# KC_BaseBoard4CompareTest-V0_2.net
KiCad netlist of a schematic drawn in Altium Designer
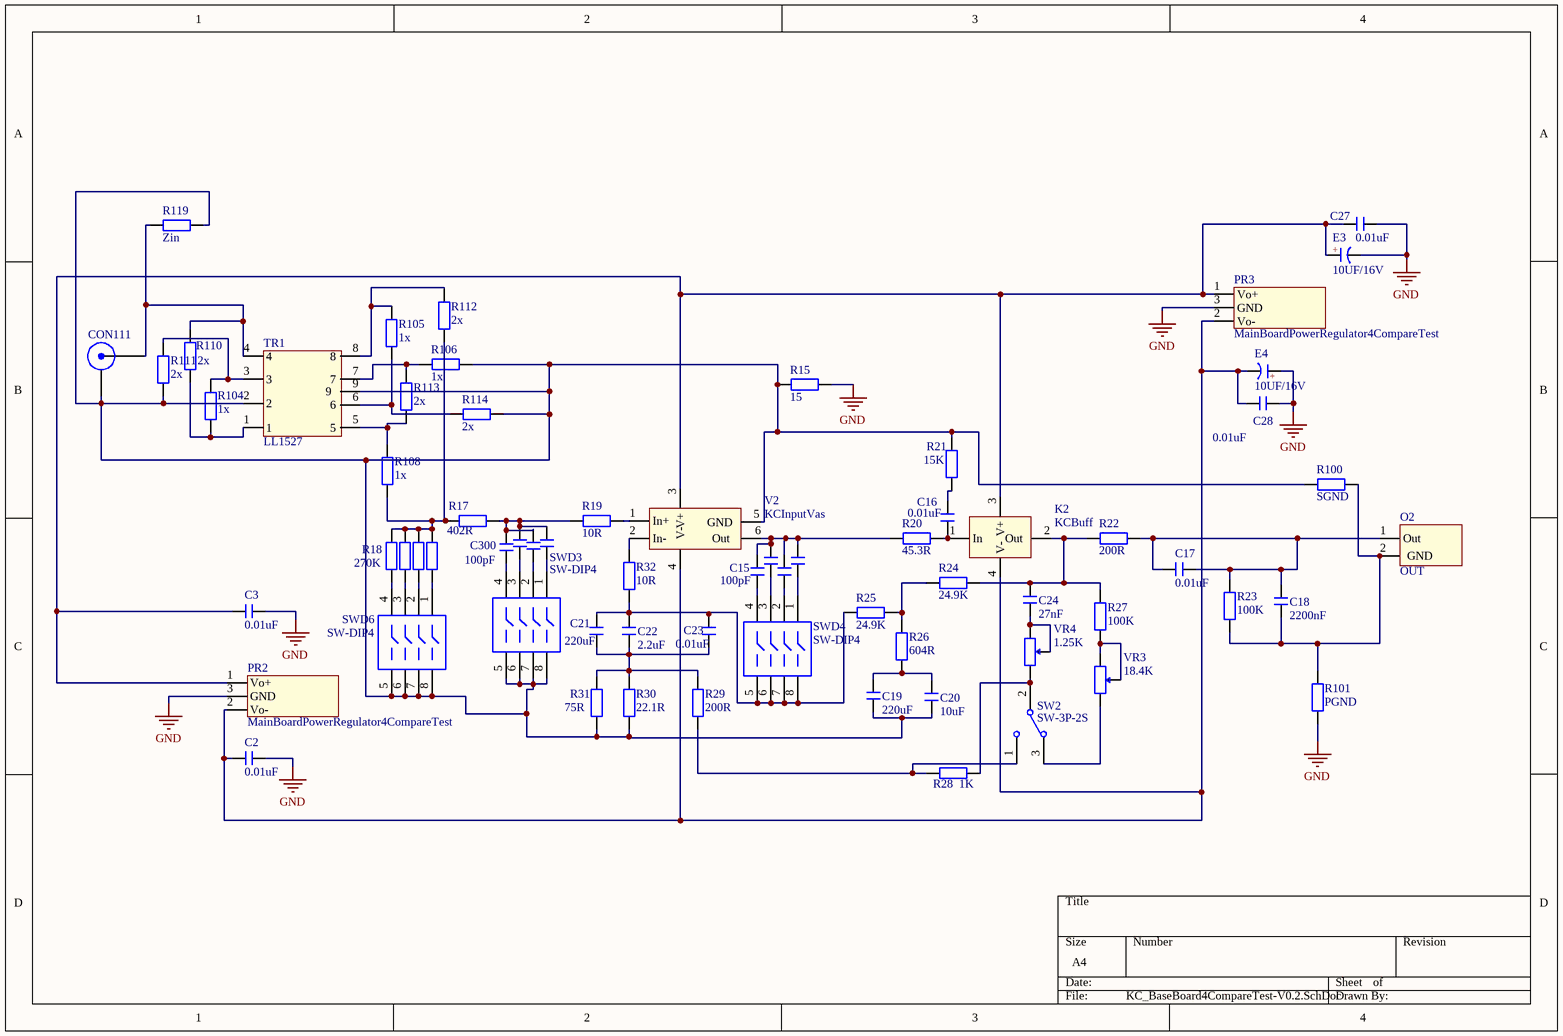
[diagram p0: KC_BaseBoard4CompareTest-V0.2.SchDoc]

(export (version "E")
  (design (tool "Eeschema 10.0.6"))
  (components
    (comp (ref "C2")
      (value "0.01uF")
      (footprint "CBB 6.3*6.3*5")
      (description "CBB电容")
      (fields (field (name "版权归属") "源创客"))
      (libsource (lib "电阻-电容-电感") (part "C-CBB"))
    )
    (comp (ref "C3")
      (value "0.01uF")
      (footprint "CBB 6.3*6.3*5")
      (description "CBB电容")
      (fields (field (name "版权归属") "源创客"))
      (libsource (lib "电阻-电容-电感") (part "C-CBB"))
    )
    (comp (ref "C15")
      (value "100pF")
      (footprint "CBB 6.3*6.3*5")
      (description "CBB电容")
      (fields (field (name "版权归属") "源创客"))
      (libsource (lib "电阻-电容-电感") (part "C-CBB"))
    )
    (comp (ref "C16")
      (value "0.01uF")
      (footprint "CBB 6.3*6.3*5")
      (description "CBB电容")
      (fields (field (name "版权归属") "源创客"))
      (libsource (lib "电阻-电容-电感") (part "C-CBB"))
    )
    (comp (ref "C17")
      (value "0.01uF")
      (footprint "CBB 6.3*6.3*5")
      (description "CBB电容")
      (fields (field (name "版权归属") "源创客"))
      (libsource (lib "电阻-电容-电感") (part "C-CBB"))
    )
    (comp (ref "C18")
      (value "2200nF")
      (footprint "CBB 6.3*6.3*5")
      (description "CBB电容")
      (fields (field (name "版权归属") "源创客"))
      (libsource (lib "电阻-电容-电感") (part "C-CBB"))
    )
    (comp (ref "C19")
      (value "220uF")
      (footprint "CBB 6.3*6.3*5")
      (description "CBB电容")
      (fields (field (name "版权归属") "源创客"))
      (libsource (lib "电阻-电容-电感") (part "C-CBB"))
    )
    (comp (ref "C20")
      (value "10uF")
      (footprint "CBB 6.3*6.3*5")
      (description "CBB电容")
      (fields (field (name "版权归属") "源创客"))
      (libsource (lib "电阻-电容-电感") (part "C-CBB"))
    )
    (comp (ref "C21")
      (value "220uF")
      (footprint "CBB 6.3*6.3*5")
      (description "CBB电容")
      (fields (field (name "版权归属") "源创客"))
      (libsource (lib "电阻-电容-电感") (part "C-CBB"))
    )
    (comp (ref "C22")
      (value "2.2uF")
      (footprint "CBB 6.3*6.3*5")
      (description "CBB电容")
      (fields (field (name "版权归属") "源创客"))
      (libsource (lib "电阻-电容-电感") (part "C-CBB"))
    )
    (comp (ref "C23")
      (value "0.01uF")
      (footprint "CBB 6.3*6.3*5")
      (description "CBB电容")
      (fields (field (name "版权归属") "源创客"))
      (libsource (lib "电阻-电容-电感") (part "C-CBB"))
    )
    (comp (ref "C24")
      (value "27nF")
      (footprint "CBB 6.3*6.3*5")
      (description "CBB电容")
      (fields (field (name "版权归属") "源创客"))
      (libsource (lib "电阻-电容-电感") (part "C-CBB"))
    )
    (comp (ref "C27")
      (value "0.01uF")
      (footprint "CBB 6.3*6.3*5")
      (description "CBB电容")
      (fields (field (name "版权归属") "源创客"))
      (libsource (lib "电阻-电容-电感") (part "C-CBB"))
    )
    (comp (ref "C28")
      (value "0.01uF")
      (footprint "CBB 6.3*6.3*5")
      (description "CBB电容")
      (fields (field (name "版权归属") "源创客"))
      (libsource (lib "电阻-电容-电感") (part "C-CBB"))
    )
    (comp (ref "C300")
      (value "100pF")
      (footprint "CBB 6.3*6.3*5")
      (description "CBB电容")
      (fields (field (name "版权归属") "源创客"))
      (libsource (lib "电阻-电容-电感") (part "C-CBB"))
    )
    (comp (ref "C301")
      (value "100pF")
      (footprint "CBB 6.3*6.3*5")
      (description "CBB电容")
      (fields (field (name "版权归属") "源创客"))
      (libsource (lib "电阻-电容-电感") (part "C-CBB"))
    )
    (comp (ref "C302")
      (value "100pF")
      (footprint "CBB 6.3*6.3*5")
      (description "CBB电容")
      (fields (field (name "版权归属") "源创客"))
      (libsource (lib "电阻-电容-电感") (part "C-CBB"))
    )
    (comp (ref "C303")
      (value "20pF")
      (footprint "CBB 6.3*6.3*5")
      (description "CBB电容")
      (fields (field (name "版权归属") "源创客"))
      (libsource (lib "电阻-电容-电感") (part "C-CBB"))
    )
    (comp (ref "C401")
      (value "100pF")
      (footprint "CBB 6.3*6.3*5")
      (description "CBB电容")
      (fields (field (name "版权归属") "源创客"))
      (libsource (lib "电阻-电容-电感") (part "C-CBB"))
    )
    (comp (ref "C402")
      (value "100pF")
      (footprint "CBB 6.3*6.3*5")
      (description "CBB电容")
      (fields (field (name "版权归属") "源创客"))
      (libsource (lib "电阻-电容-电感") (part "C-CBB"))
    )
    (comp (ref "C403")
      (value "20pF")
      (footprint "CBB 6.3*6.3*5")
      (description "CBB电容")
      (fields (field (name "版权归属") "源创客"))
      (libsource (lib "电阻-电容-电感") (part "C-CBB"))
    )
    (comp (ref "CON111")
      (value "RCA")
      (footprint "SMB_V-RJ45")
      (description "RCA Connector")
      (fields (field (name "PUBLISHER") "Altium Limited"))
      (libsource (lib "Connectors") (part "RCA"))
    )
    (comp (ref "E3")
      (value "10UF/16V")
      (footprint "CAP 1.5*4*8")
      (description "直插电解电容")
      (fields (field (name "版权归属") "源创客"))
      (libsource (lib "电阻-电容-电感") (part "C-CAP"))
    )
    (comp (ref "E4")
      (value "10UF/16V")
      (footprint "CAP 1.5*4*8")
      (description "直插电解电容")
      (fields (field (name "版权归属") "源创客"))
      (libsource (lib "电阻-电容-电感") (part "C-CAP"))
    )
    (comp (ref "K2")
      (value "KCBuff")
      (footprint "KCBuff_M4")
      (description "King Cello Buffer Stage")
      (libsource (lib "KC_amp") (part "KCBuff"))
    )
    (comp (ref "O2")
      (value "OUT")
      (footprint "Signal_Terminal")
      (description "Signal Out")
      (libsource (lib "KC_amp") (part "Signal_Out"))
    )
    (comp (ref "PR2")
      (value "MainBoardPowerRegulator4CompareTest")
      (footprint "KC_MBPowerReg4Compare-1.5mm")
      (description "King Cello Compare Test Power")
      (libsource (lib "KC_amp") (part "MainBoardPowerRegulator4CompareTest"))
    )
    (comp (ref "PR3")
      (value "MainBoardPowerRegulator4CompareTest")
      (footprint "KC_MBPowerReg4Compare-1.5mm")
      (description "King Cello Compare Test Power")
      (libsource (lib "KC_amp") (part "MainBoardPowerRegulator4CompareTest"))
    )
    (comp (ref "R15")
      (value "15")
      (footprint "RS 1/4W")
      (description "直插色环电阻")
      (fields (field (name "版权归属") "源创客"))
      (libsource (lib "电阻-电容-电感") (part "R-CRR"))
    )
    (comp (ref "R17")
      (value "402R")
      (footprint "RS 1/4W")
      (description "直插色环电阻")
      (fields (field (name "版权归属") "源创客"))
      (libsource (lib "电阻-电容-电感") (part "R-CRR"))
    )
    (comp (ref "R18")
      (value "270K")
      (footprint "RS 1/4W")
      (description "直插色环电阻")
      (fields (field (name "版权归属") "源创客"))
      (libsource (lib "电阻-电容-电感") (part "R-CRR"))
    )
    (comp (ref "R19")
      (value "10R")
      (footprint "RS 1/4W")
      (description "直插色环电阻")
      (fields (field (name "版权归属") "源创客"))
      (libsource (lib "电阻-电容-电感") (part "R-CRR"))
    )
    (comp (ref "R20")
      (value "45.3R")
      (footprint "RS 1/4W")
      (description "直插色环电阻")
      (fields (field (name "版权归属") "源创客"))
      (libsource (lib "电阻-电容-电感") (part "R-CRR"))
    )
    (comp (ref "R21")
      (value "15K")
      (footprint "RS 1/4W")
      (description "直插色环电阻")
      (fields (field (name "版权归属") "源创客"))
      (libsource (lib "电阻-电容-电感") (part "R-CRR"))
    )
    (comp (ref "R22")
      (value "200R")
      (footprint "RS 1/4W")
      (description "直插色环电阻")
      (fields (field (name "版权归属") "源创客"))
      (libsource (lib "电阻-电容-电感") (part "R-CRR"))
    )
    (comp (ref "R23")
      (value "100K")
      (footprint "RS 1/4W")
      (description "直插色环电阻")
      (fields (field (name "版权归属") "源创客"))
      (libsource (lib "电阻-电容-电感") (part "R-CRR"))
    )
    (comp (ref "R24")
      (value "24.9K")
      (footprint "RS 1/4W")
      (description "直插色环电阻")
      (fields (field (name "版权归属") "源创客"))
      (libsource (lib "电阻-电容-电感") (part "R-CRR"))
    )
    (comp (ref "R25")
      (value "24.9K")
      (footprint "RS 1/4W")
      (description "直插色环电阻")
      (fields (field (name "版权归属") "源创客"))
      (libsource (lib "电阻-电容-电感") (part "R-CRR"))
    )
    (comp (ref "R26")
      (value "604R")
      (footprint "RS 1/4W")
      (description "直插色环电阻")
      (fields (field (name "版权归属") "源创客"))
      (libsource (lib "电阻-电容-电感") (part "R-CRR"))
    )
    (comp (ref "R27")
      (value "100K")
      (footprint "RS 1/4W")
      (description "直插色环电阻")
      (fields (field (name "版权归属") "源创客"))
      (libsource (lib "电阻-电容-电感") (part "R-CRR"))
    )
    (comp (ref "R28")
      (value "1K")
      (footprint "RS 1/4W")
      (description "直插色环电阻")
      (fields (field (name "版权归属") "源创客"))
      (libsource (lib "电阻-电容-电感") (part "R-CRR"))
    )
    (comp (ref "R29")
      (value "200R")
      (footprint "RS 1/4W")
      (description "直插色环电阻")
      (fields (field (name "版权归属") "源创客"))
      (libsource (lib "电阻-电容-电感") (part "R-CRR"))
    )
    (comp (ref "R30")
      (value "22.1R")
      (footprint "RS 1/4W")
      (description "直插色环电阻")
      (fields (field (name "版权归属") "源创客"))
      (libsource (lib "电阻-电容-电感") (part "R-CRR"))
    )
    (comp (ref "R31")
      (value "75R")
      (footprint "RS 1/4W")
      (description "直插色环电阻")
      (fields (field (name "版权归属") "源创客"))
      (libsource (lib "电阻-电容-电感") (part "R-CRR"))
    )
    (comp (ref "R32")
      (value "10R")
      (footprint "RS 1/4W")
      (description "直插色环电阻")
      (fields (field (name "版权归属") "源创客"))
      (libsource (lib "电阻-电容-电感") (part "R-CRR"))
    )
    (comp (ref "R100")
      (value "SGND")
      (footprint "RS 1/4W")
      (description "直插色环电阻")
      (fields (field (name "版权归属") "源创客"))
      (libsource (lib "电阻-电容-电感") (part "R-CRR"))
    )
    (comp (ref "R101")
      (value "PGND")
      (footprint "RS 1/4W")
      (description "直插色环电阻")
      (fields (field (name "版权归属") "源创客"))
      (libsource (lib "电阻-电容-电感") (part "R-CRR"))
    )
    (comp (ref "R104")
      (value "1x")
      (footprint "RS 1/4W")
      (description "直插色环电阻")
      (fields (field (name "版权归属") "源创客"))
      (libsource (lib "电阻-电容-电感") (part "R-CRR"))
    )
    (comp (ref "R105")
      (value "1x")
      (footprint "RS 1/4W")
      (description "直插色环电阻")
      (fields (field (name "版权归属") "源创客"))
      (libsource (lib "电阻-电容-电感") (part "R-CRR"))
    )
    (comp (ref "R106")
      (value "1x")
      (footprint "RS 1/4W")
      (description "直插色环电阻")
      (fields (field (name "版权归属") "源创客"))
      (libsource (lib "电阻-电容-电感") (part "R-CRR"))
    )
    (comp (ref "R108")
      (value "1x")
      (footprint "RS 1/4W")
      (description "直插色环电阻")
      (fields (field (name "版权归属") "源创客"))
      (libsource (lib "电阻-电容-电感") (part "R-CRR"))
    )
    (comp (ref "R110")
      (value "2x")
      (footprint "RS 1/4W")
      (description "直插色环电阻")
      (fields (field (name "版权归属") "源创客"))
      (libsource (lib "电阻-电容-电感") (part "R-CRR"))
    )
    (comp (ref "R111")
      (value "2x")
      (footprint "RS 1/4W")
      (description "直插色环电阻")
      (fields (field (name "版权归属") "源创客"))
      (libsource (lib "电阻-电容-电感") (part "R-CRR"))
    )
    (comp (ref "R112")
      (value "2x")
      (footprint "RS 1/4W")
      (description "直插色环电阻")
      (fields (field (name "版权归属") "源创客"))
      (libsource (lib "电阻-电容-电感") (part "R-CRR"))
    )
    (comp (ref "R113")
      (value "2x")
      (footprint "RS 1/4W")
      (description "直插色环电阻")
      (fields (field (name "版权归属") "源创客"))
      (libsource (lib "电阻-电容-电感") (part "R-CRR"))
    )
    (comp (ref "R114")
      (value "2x")
      (footprint "RS 1/4W")
      (description "直插色环电阻")
      (fields (field (name "版权归属") "源创客"))
      (libsource (lib "电阻-电容-电感") (part "R-CRR"))
    )
    (comp (ref "R119")
      (value "Zin")
      (footprint "RS 1/4W")
      (description "直插色环电阻")
      (fields (field (name "版权归属") "源创客"))
      (libsource (lib "电阻-电容-电感") (part "R-CRR"))
    )
    (comp (ref "R181")
      (value "182K")
      (footprint "RS 1/4W")
      (description "直插色环电阻")
      (fields (field (name "版权归属") "源创客"))
      (libsource (lib "电阻-电容-电感") (part "R-CRR"))
    )
    (comp (ref "R182")
      (value "100K")
      (footprint "RS 1/4W")
      (description "直插色环电阻")
      (fields (field (name "版权归属") "源创客"))
      (libsource (lib "电阻-电容-电感") (part "R-CRR"))
    )
    (comp (ref "R183")
      (value "47K")
      (footprint "RS 1/4W")
      (description "直插色环电阻")
      (fields (field (name "版权归属") "源创客"))
      (libsource (lib "电阻-电容-电感") (part "R-CRR"))
    )
    (comp (ref "SW2")
      (value "SW-3P-2S")
      (footprint "SS-12D06")
      (description "3 Pin 2 Switch")
      (libsource (lib "Connectors") (part "SW-3P-2S"))
    )
    (comp (ref "SWD3")
      (value "SW-DIP4")
      (footprint "DIP-8")
      (description "DIP Switch")
      (fields (field (name "PUBLISHER") "Altium Limited"))
      (libsource (lib "Miscellaneous Devices") (part "SW-DIP4"))
    )
    (comp (ref "SWD4")
      (value "SW-DIP4")
      (footprint "DIP-8")
      (description "DIP Switch")
      (fields (field (name "PUBLISHER") "Altium Limited"))
      (libsource (lib "Miscellaneous Devices") (part "SW-DIP4"))
    )
    (comp (ref "SWD6")
      (value "SW-DIP4")
      (footprint "DIP-8")
      (description "DIP Switch")
      (fields (field (name "PUBLISHER") "Altium Limited"))
      (libsource (lib "Miscellaneous Devices") (part "SW-DIP4"))
    )
    (comp (ref "TR1")
      (value "LL1527")
      (footprint "LL1527")
      (description "Lundahl LL1527")
      (libsource (lib "KC_amp") (part "LL1527"))
    )
    (comp (ref "V2")
      (value "KCInputVas")
      (footprint "KCIn_VAS_M4")
      (description "King Cello Input Stage and VAS")
      (libsource (lib "KC_amp") (part "KCInputVas"))
    )
    (comp (ref "VR3")
      (value "18.4K")
      (footprint "RS 1/2W-VR")
      (description "直插可调电阻-顶调")
      (libsource (lib "电阻-电容-电感") (part "VR-W"))
    )
    (comp (ref "VR4")
      (value "1.25K")
      (footprint "RS 1/2W-VR")
      (description "直插可调电阻-顶调")
      (libsource (lib "电阻-电容-电感") (part "VR-W"))
    )
  )
  (nets
    (net (code "1") (name "GND") (class "Default")
      (node (ref "C2") (pin "2") (pinfunction "2_2") (pintype "passive"))
      (node (ref "C27") (pin "2") (pinfunction "2_2") (pintype "passive"))
      (node (ref "C28") (pin "2") (pinfunction "2_2") (pintype "passive"))
      (node (ref "C3") (pin "2") (pinfunction "2_2") (pintype "passive"))
      (node (ref "E3") (pin "2") (pinfunction "K_2") (pintype "passive"))
      (node (ref "E4") (pin "1") (pinfunction "A_1") (pintype "passive"))
      (node (ref "PR2") (pin "3") (pinfunction "GND_3") (pintype "passive"))
      (node (ref "PR3") (pin "3") (pinfunction "GND_3") (pintype "passive"))
      (node (ref "R101") (pin "1") (pinfunction "1_1") (pintype "passive"))
      (node (ref "R15") (pin "2") (pinfunction "2_2") (pintype "passive"))
    )
    (net (code "2") (name "Net-(C15-Pad1)") (class "Default")
      (node (ref "C15") (pin "1") (pinfunction "1_1") (pintype "passive"))
      (node (ref "SWD4") (pin "4") (pinfunction "4_4") (pintype "passive"))
    )
    (net (code "3") (name "Net-(C16-Pad2)") (class "Default")
      (node (ref "C16") (pin "2") (pinfunction "2_2") (pintype "passive"))
      (node (ref "R21") (pin "1") (pinfunction "1_1") (pintype "passive"))
    )
    (net (code "4") (name "Net-(C19-Pad1)") (class "Default")
      (node (ref "C19") (pin "1") (pinfunction "1_1") (pintype "passive"))
      (node (ref "C20") (pin "1") (pinfunction "1_1") (pintype "passive"))
      (node (ref "R26") (pin "1") (pinfunction "1_1") (pintype "passive"))
    )
    (net (code "5") (name "Net-(C21-Pad1)") (class "Default")
      (node (ref "C21") (pin "1") (pinfunction "1_1") (pintype "passive"))
      (node (ref "C22") (pin "1") (pinfunction "1_1") (pintype "passive"))
      (node (ref "C23") (pin "1") (pinfunction "1_1") (pintype "passive"))
      (node (ref "R25") (pin "1") (pinfunction "1_1") (pintype "passive"))
      (node (ref "R32") (pin "1") (pinfunction "1_1") (pintype "passive"))
      (node (ref "SWD4") (pin "5") (pinfunction "5_5") (pintype "passive"))
      (node (ref "SWD4") (pin "6") (pinfunction "6_6") (pintype "passive"))
      (node (ref "SWD4") (pin "7") (pinfunction "7_7") (pintype "passive"))
      (node (ref "SWD4") (pin "8") (pinfunction "8_8") (pintype "passive"))
    )
    (net (code "6") (name "Net-(C21-Pad2)") (class "Default")
      (node (ref "C21") (pin "2") (pinfunction "2_2") (pintype "passive"))
      (node (ref "C22") (pin "2") (pinfunction "2_2") (pintype "passive"))
      (node (ref "C23") (pin "2") (pinfunction "2_2") (pintype "passive"))
      (node (ref "R29") (pin "2") (pinfunction "2_2") (pintype "passive"))
      (node (ref "R30") (pin "2") (pinfunction "2_2") (pintype "passive"))
      (node (ref "R31") (pin "2") (pinfunction "2_2") (pintype "passive"))
    )
    (net (code "7") (name "Net-(C24-Pad2)") (class "Default")
      (node (ref "C24") (pin "2") (pinfunction "2_2") (pintype "passive"))
      (node (ref "VR4") (pin "1") (pinfunction "1_1") (pintype "passive"))
      (node (ref "VR4") (pin "3") (pinfunction "3_3") (pintype "passive"))
    )
    (net (code "8") (name "Net-(C300-Pad1)") (class "Default")
      (node (ref "C300") (pin "1") (pinfunction "1_1") (pintype "passive"))
      (node (ref "SWD3") (pin "4") (pinfunction "4_4") (pintype "passive"))
    )
    (net (code "9") (name "Net-(C300-Pad2)") (class "Default")
      (node (ref "C300") (pin "2") (pinfunction "2_2") (pintype "passive"))
      (node (ref "C301") (pin "2") (pinfunction "2_2") (pintype "passive"))
      (node (ref "C302") (pin "2") (pinfunction "2_2") (pintype "passive"))
      (node (ref "C303") (pin "2") (pinfunction "2_2") (pintype "passive"))
      (node (ref "R17") (pin "2") (pinfunction "2_2") (pintype "passive"))
      (node (ref "R19") (pin "1") (pinfunction "1_1") (pintype "passive"))
    )
    (net (code "10") (name "Net-(C301-Pad1)") (class "Default")
      (node (ref "C301") (pin "1") (pinfunction "1_1") (pintype "passive"))
      (node (ref "SWD3") (pin "3") (pinfunction "3_3") (pintype "passive"))
    )
    (net (code "11") (name "Net-(C302-Pad1)") (class "Default")
      (node (ref "C302") (pin "1") (pinfunction "1_1") (pintype "passive"))
      (node (ref "SWD3") (pin "2") (pinfunction "2_2") (pintype "passive"))
    )
    (net (code "12") (name "Net-(C303-Pad1)") (class "Default")
      (node (ref "C303") (pin "1") (pinfunction "1_1") (pintype "passive"))
      (node (ref "SWD3") (pin "1") (pinfunction "1_1") (pintype "passive"))
    )
    (net (code "13") (name "Net-(C401-Pad1)") (class "Default")
      (node (ref "C401") (pin "1") (pinfunction "1_1") (pintype "passive"))
      (node (ref "SWD4") (pin "3") (pinfunction "3_3") (pintype "passive"))
    )
    (net (code "14") (name "Net-(C402-Pad1)") (class "Default")
      (node (ref "C402") (pin "1") (pinfunction "1_1") (pintype "passive"))
      (node (ref "SWD4") (pin "2") (pinfunction "2_2") (pintype "passive"))
    )
    (net (code "15") (name "Net-(C403-Pad1)") (class "Default")
      (node (ref "C403") (pin "1") (pinfunction "1_1") (pintype "passive"))
      (node (ref "SWD4") (pin "1") (pinfunction "1_1") (pintype "passive"))
    )
    (net (code "16") (name "Net-(CON111-X)") (class "Default")
      (node (ref "CON111") (pin "1") (pinfunction "X_1") (pintype "passive"))
      (node (ref "R110") (pin "2") (pinfunction "2_2") (pintype "passive"))
      (node (ref "R119") (pin "1") (pinfunction "1_1") (pintype "passive"))
      (node (ref "TR1") (pin "4") (pinfunction "4_4") (pintype "passive"))
    )
    (net (code "17") (name "Net-(CON111-Y)") (class "Default")
      (node (ref "C19") (pin "2") (pinfunction "2_2") (pintype "passive"))
      (node (ref "C20") (pin "2") (pinfunction "2_2") (pintype "passive"))
      (node (ref "CON111") (pin "2") (pinfunction "Y_2") (pintype "passive"))
      (node (ref "R100") (pin "1") (pinfunction "1_1") (pintype "passive"))
      (node (ref "R106") (pin "2") (pinfunction "2_2") (pintype "passive"))
      (node (ref "R111") (pin "1") (pinfunction "1_1") (pintype "passive"))
      (node (ref "R114") (pin "2") (pinfunction "2_2") (pintype "passive"))
      (node (ref "R119") (pin "2") (pinfunction "2_2") (pintype "passive"))
      (node (ref "R15") (pin "1") (pinfunction "1_1") (pintype "passive"))
      (node (ref "R21") (pin "2") (pinfunction "2_2") (pintype "passive"))
      (node (ref "R30") (pin "1") (pinfunction "1_1") (pintype "passive"))
      (node (ref "R31") (pin "1") (pinfunction "1_1") (pintype "passive"))
      (node (ref "SWD3") (pin "5") (pinfunction "5_5") (pintype "passive"))
      (node (ref "SWD3") (pin "6") (pinfunction "6_6") (pintype "passive"))
      (node (ref "SWD3") (pin "7") (pinfunction "7_7") (pintype "passive"))
      (node (ref "SWD3") (pin "8") (pinfunction "8_8") (pintype "passive"))
      (node (ref "SWD6") (pin "5") (pinfunction "5_5") (pintype "passive"))
      (node (ref "SWD6") (pin "6") (pinfunction "6_6") (pintype "passive"))
      (node (ref "SWD6") (pin "7") (pinfunction "7_7") (pintype "passive"))
      (node (ref "SWD6") (pin "8") (pinfunction "8_8") (pintype "passive"))
      (node (ref "TR1") (pin "2") (pinfunction "2_2") (pintype "passive"))
      (node (ref "TR1") (pin "9") (pinfunction "9_9") (pintype "passive"))
      (node (ref "V2") (pin "5") (pinfunction "GND_5") (pintype "passive"))
    )
    (net (code "18") (name "Net-(E3-A)") (class "Default")
      (node (ref "C27") (pin "1") (pinfunction "1_1") (pintype "passive"))
      (node (ref "C3") (pin "1") (pinfunction "1_1") (pintype "passive"))
      (node (ref "E3") (pin "1") (pinfunction "A_1") (pintype "passive"))
      (node (ref "K2") (pin "3") (pinfunction "V+_3") (pintype "passive"))
      (node (ref "PR2") (pin "1") (pinfunction "Vo+_1") (pintype "passive"))
      (node (ref "PR3") (pin "1") (pinfunction "Vo+_1") (pintype "passive"))
      (node (ref "V2") (pin "3") (pinfunction "V+_3") (pintype "passive"))
    )
    (net (code "19") (name "Net-(E4-K)") (class "Default")
      (node (ref "C2") (pin "1") (pinfunction "1_1") (pintype "passive"))
      (node (ref "C28") (pin "1") (pinfunction "1_1") (pintype "passive"))
      (node (ref "E4") (pin "2") (pinfunction "K_2") (pintype "passive"))
      (node (ref "K2") (pin "4") (pinfunction "V-_4") (pintype "passive"))
      (node (ref "PR2") (pin "2") (pinfunction "Vo-_2") (pintype "passive"))
      (node (ref "PR3") (pin "2") (pinfunction "Vo-_2") (pintype "passive"))
      (node (ref "V2") (pin "4") (pinfunction "V-_4") (pintype "passive"))
    )
    (net (code "20") (name "Net-(K2-In)") (class "Default")
      (node (ref "C16") (pin "1") (pinfunction "1_1") (pintype "passive"))
      (node (ref "K2") (pin "1") (pinfunction "In_1") (pintype "passive"))
      (node (ref "R20") (pin "2") (pinfunction "2_2") (pintype "passive"))
    )
    (net (code "21") (name "Net-(K2-Out)") (class "Default")
      (node (ref "C24") (pin "1") (pinfunction "1_1") (pintype "passive"))
      (node (ref "K2") (pin "2") (pinfunction "Out_2") (pintype "passive"))
      (node (ref "R22") (pin "2") (pinfunction "2_2") (pintype "passive"))
      (node (ref "R24") (pin "2") (pinfunction "2_2") (pintype "passive"))
      (node (ref "R27") (pin "1") (pinfunction "1_1") (pintype "passive"))
    )
    (net (code "22") (name "Net-(O2-GND)") (class "Default")
      (node (ref "C18") (pin "2") (pinfunction "2_2") (pintype "passive"))
      (node (ref "O2") (pin "2") (pinfunction "GND_2") (pintype "passive"))
      (node (ref "R100") (pin "2") (pinfunction "2_2") (pintype "passive"))
      (node (ref "R101") (pin "2") (pinfunction "2_2") (pintype "passive"))
      (node (ref "R23") (pin "2") (pinfunction "2_2") (pintype "passive"))
    )
    (net (code "23") (name "Net-(O2-Out)") (class "Default")
      (node (ref "C17") (pin "1") (pinfunction "1_1") (pintype "passive"))
      (node (ref "C17") (pin "2") (pinfunction "2_2") (pintype "passive"))
      (node (ref "C18") (pin "1") (pinfunction "1_1") (pintype "passive"))
      (node (ref "O2") (pin "1") (pinfunction "Out_1") (pintype "passive"))
      (node (ref "R22") (pin "1") (pinfunction "1_1") (pintype "passive"))
      (node (ref "R23") (pin "1") (pinfunction "1_1") (pintype "passive"))
    )
    (net (code "24") (name "Net-(R18-Pad1)") (class "Default")
      (node (ref "R18") (pin "1") (pinfunction "1_1") (pintype "passive"))
      (node (ref "SWD6") (pin "4") (pinfunction "4_4") (pintype "passive"))
    )
    (net (code "25") (name "Net-(R24-Pad1)") (class "Default")
      (node (ref "R24") (pin "1") (pinfunction "1_1") (pintype "passive"))
      (node (ref "R25") (pin "2") (pinfunction "2_2") (pintype "passive"))
      (node (ref "R26") (pin "2") (pinfunction "2_2") (pintype "passive"))
    )
    (net (code "26") (name "Net-(R27-Pad2)") (class "Default")
      (node (ref "R27") (pin "2") (pinfunction "2_2") (pintype "passive"))
      (node (ref "VR3") (pin "1") (pinfunction "1_1") (pintype "passive"))
      (node (ref "VR3") (pin "3") (pinfunction "3_3") (pintype "passive"))
    )
    (net (code "27") (name "Net-(R28-Pad1)") (class "Default")
      (node (ref "R28") (pin "1") (pinfunction "1_1") (pintype "passive"))
      (node (ref "R29") (pin "1") (pinfunction "1_1") (pintype "passive"))
      (node (ref "SW2") (pin "1") (pinfunction "1_1") (pintype "passive"))
    )
    (net (code "28") (name "Net-(R28-Pad2)") (class "Default")
      (node (ref "R28") (pin "2") (pinfunction "2_2") (pintype "passive"))
      (node (ref "SW2") (pin "2") (pinfunction "2_2") (pintype "passive"))
      (node (ref "VR4") (pin "2") (pinfunction "2_2") (pintype "passive"))
    )
    (net (code "29") (name "Net-(R104-Pad1)") (class "Default")
      (node (ref "R104") (pin "1") (pinfunction "1_1") (pintype "passive"))
      (node (ref "R110") (pin "1") (pinfunction "1_1") (pintype "passive"))
      (node (ref "TR1") (pin "1") (pinfunction "1_1") (pintype "passive"))
    )
    (net (code "30") (name "Net-(R104-Pad2)") (class "Default")
      (node (ref "R104") (pin "2") (pinfunction "2_2") (pintype "passive"))
      (node (ref "R111") (pin "2") (pinfunction "2_2") (pintype "passive"))
      (node (ref "TR1") (pin "3") (pinfunction "3_3") (pintype "passive"))
    )
    (net (code "31") (name "Net-(R105-Pad1)") (class "Default")
      (node (ref "R105") (pin "1") (pinfunction "1_1") (pintype "passive"))
      (node (ref "R114") (pin "1") (pinfunction "1_1") (pintype "passive"))
      (node (ref "TR1") (pin "6") (pinfunction "6_6") (pintype "passive"))
    )
    (net (code "32") (name "Net-(R105-Pad2)") (class "Default")
      (node (ref "R105") (pin "2") (pinfunction "2_2") (pintype "passive"))
      (node (ref "R112") (pin "2") (pinfunction "2_2") (pintype "passive"))
      (node (ref "TR1") (pin "8") (pinfunction "8_8") (pintype "passive"))
    )
    (net (code "33") (name "Net-(R106-Pad1)") (class "Default")
      (node (ref "R106") (pin "1") (pinfunction "1_1") (pintype "passive"))
      (node (ref "R113") (pin "2") (pinfunction "2_2") (pintype "passive"))
      (node (ref "TR1") (pin "7") (pinfunction "7_7") (pintype "passive"))
    )
    (net (code "34") (name "Net-(R108-Pad1)") (class "Default")
      (node (ref "R108") (pin "1") (pinfunction "1_1") (pintype "passive"))
      (node (ref "R112") (pin "1") (pinfunction "1_1") (pintype "passive"))
      (node (ref "R17") (pin "1") (pinfunction "1_1") (pintype "passive"))
      (node (ref "R18") (pin "2") (pinfunction "2_2") (pintype "passive"))
      (node (ref "R181") (pin "2") (pinfunction "2_2") (pintype "passive"))
      (node (ref "R182") (pin "2") (pinfunction "2_2") (pintype "passive"))
      (node (ref "R183") (pin "2") (pinfunction "2_2") (pintype "passive"))
    )
    (net (code "35") (name "Net-(R108-Pad2)") (class "Default")
      (node (ref "R108") (pin "2") (pinfunction "2_2") (pintype "passive"))
      (node (ref "R113") (pin "1") (pinfunction "1_1") (pintype "passive"))
      (node (ref "TR1") (pin "5") (pinfunction "5_5") (pintype "passive"))
    )
    (net (code "36") (name "Net-(R181-Pad1)") (class "Default")
      (node (ref "R181") (pin "1") (pinfunction "1_1") (pintype "passive"))
      (node (ref "SWD6") (pin "3") (pinfunction "3_3") (pintype "passive"))
    )
    (net (code "37") (name "Net-(R182-Pad1)") (class "Default")
      (node (ref "R182") (pin "1") (pinfunction "1_1") (pintype "passive"))
      (node (ref "SWD6") (pin "2") (pinfunction "2_2") (pintype "passive"))
    )
    (net (code "38") (name "Net-(R183-Pad1)") (class "Default")
      (node (ref "R183") (pin "1") (pinfunction "1_1") (pintype "passive"))
      (node (ref "SWD6") (pin "1") (pinfunction "1_1") (pintype "passive"))
    )
    (net (code "39") (name "Net-(SW2-Pad3)") (class "Default")
      (node (ref "SW2") (pin "3") (pinfunction "3_3") (pintype "passive"))
      (node (ref "VR3") (pin "2") (pinfunction "2_2") (pintype "passive"))
    )
    (net (code "40") (name "Net-(V2-In+)") (class "Default")
      (node (ref "R19") (pin "2") (pinfunction "2_2") (pintype "passive"))
      (node (ref "V2") (pin "1") (pinfunction "In+_1") (pintype "passive"))
    )
    (net (code "41") (name "Net-(V2-In-)") (class "Default")
      (node (ref "R32") (pin "2") (pinfunction "2_2") (pintype "passive"))
      (node (ref "V2") (pin "2") (pinfunction "In-_2") (pintype "passive"))
    )
    (net (code "42") (name "Net-(V2-Out)") (class "Default")
      (node (ref "C15") (pin "2") (pinfunction "2_2") (pintype "passive"))
      (node (ref "C401") (pin "2") (pinfunction "2_2") (pintype "passive"))
      (node (ref "C402") (pin "2") (pinfunction "2_2") (pintype "passive"))
      (node (ref "C403") (pin "2") (pinfunction "2_2") (pintype "passive"))
      (node (ref "R20") (pin "1") (pinfunction "1_1") (pintype "passive"))
      (node (ref "V2") (pin "6") (pinfunction "Out_6") (pintype "passive"))
    )
  )
)
